# timetracker-1-5.net
KiCad netlist of a schematic drawn in EAGLE
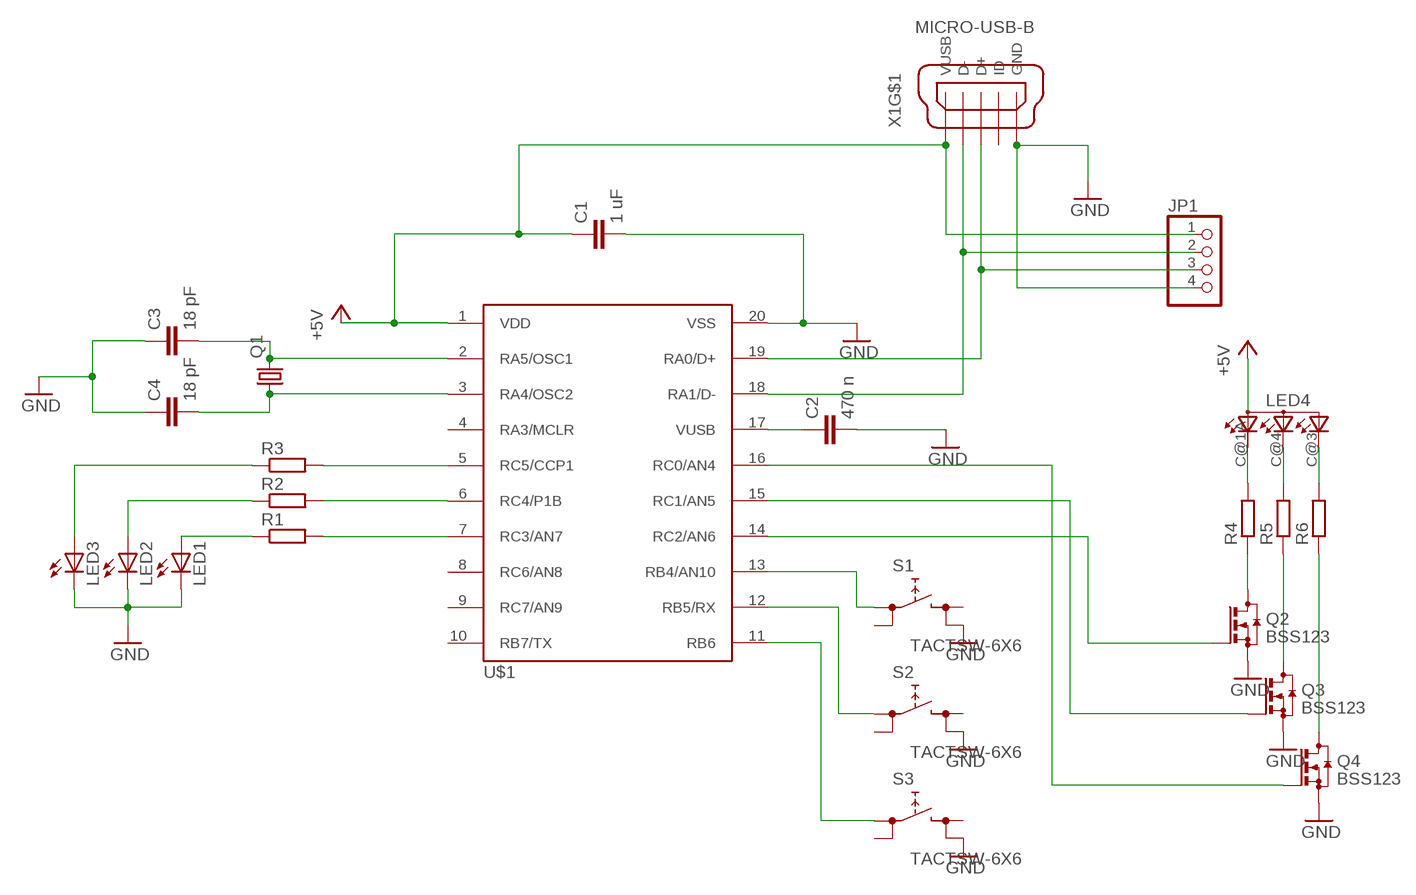
[diagram p0: schematic, sheet 1]

(export (version "E")
  (design (tool "Eeschema 10.0.6"))
  (components
    (comp (ref "C1")
      (value "1 uF")
      (footprint "eagle-import:C0805")
      (libsource (lib "eagle-import") (part "C-EUC0805"))
    )
    (comp (ref "C2")
      (value "470 n")
      (footprint "eagle-import:C0805")
      (libsource (lib "eagle-import") (part "C-EUC0805"))
    )
    (comp (ref "C3")
      (value "18 pF")
      (footprint "eagle-import:C0805")
      (libsource (lib "eagle-import") (part "C-EUC0805"))
    )
    (comp (ref "C4")
      (value "18 pF")
      (footprint "eagle-import:C0805")
      (libsource (lib "eagle-import") (part "C-EUC0805"))
    )
    (comp (ref "JP1")
      (value "PINHD-1X4")
      (footprint "eagle-import:1X04")
      (libsource (lib "eagle-import") (part "PINHD-1X4"))
    )
    (comp (ref "LED1")
      (value "LEDSML0805")
      (footprint "eagle-import:SML0805")
      (libsource (lib "eagle-import") (part "LEDSML0805"))
    )
    (comp (ref "LED2")
      (value "LEDSML0805")
      (footprint "eagle-import:SML0805")
      (libsource (lib "eagle-import") (part "LEDSML0805"))
    )
    (comp (ref "LED3")
      (value "LEDSML0805")
      (footprint "eagle-import:SML0805")
      (libsource (lib "eagle-import") (part "LEDSML0805"))
    )
    (comp (ref "LED4")
      (value "RGBLED-3P-LCC-4")
      (footprint "eagle-import:P-LCC-4")
      (libsource (lib "eagle-import") (part "RGBLED-3P-LCC-4"))
    )
    (comp (ref "Q1")
      (value "CRYSTALHC49UP")
      (footprint "eagle-import:HC49UP")
      (libsource (lib "eagle-import") (part "CRYSTALHC49UP"))
    )
    (comp (ref "Q2")
      (value "BSS123")
      (footprint "eagle-import:SOT23")
      (libsource (lib "eagle-import") (part "BSS123"))
    )
    (comp (ref "Q3")
      (value "BSS123")
      (footprint "eagle-import:SOT23")
      (libsource (lib "eagle-import") (part "BSS123"))
    )
    (comp (ref "Q4")
      (value "BSS123")
      (footprint "eagle-import:SOT23")
      (libsource (lib "eagle-import") (part "BSS123"))
    )
    (comp (ref "R1")
      (value "R-EU_R0805")
      (footprint "eagle-import:R0805")
      (libsource (lib "eagle-import") (part "R-EU_R0805"))
    )
    (comp (ref "R2")
      (value "R-EU_R0805")
      (footprint "eagle-import:R0805")
      (libsource (lib "eagle-import") (part "R-EU_R0805"))
    )
    (comp (ref "R3")
      (value "R-EU_R0805")
      (footprint "eagle-import:R0805")
      (libsource (lib "eagle-import") (part "R-EU_R0805"))
    )
    (comp (ref "R4")
      (value "R-EU_R0805")
      (footprint "eagle-import:R0805")
      (libsource (lib "eagle-import") (part "R-EU_R0805"))
    )
    (comp (ref "R5")
      (value "R-EU_R0805")
      (footprint "eagle-import:R0805")
      (libsource (lib "eagle-import") (part "R-EU_R0805"))
    )
    (comp (ref "R6")
      (value "R-EU_R0805")
      (footprint "eagle-import:R0805")
      (libsource (lib "eagle-import") (part "R-EU_R0805"))
    )
    (comp (ref "S1")
      (value "TACTSW-6X6")
      (footprint "eagle-import:TACTSW-6X6")
      (libsource (lib "eagle-import") (part "TACTSW-6X6"))
    )
    (comp (ref "S2")
      (value "TACTSW-6X6")
      (footprint "eagle-import:TACTSW-6X6")
      (libsource (lib "eagle-import") (part "TACTSW-6X6"))
    )
    (comp (ref "S3")
      (value "TACTSW-6X6")
      (footprint "eagle-import:TACTSW-6X6")
      (libsource (lib "eagle-import") (part "TACTSW-6X6"))
    )
    (comp (ref "U$1")
      (value "PIC18F14K50SMD")
      (footprint "eagle-import:DIL20-SMD")
      (libsource (lib "eagle-import") (part "PIC18F14K50SMD"))
    )
    (comp (ref "X1")
      (value "MICRO-USB-B")
      (footprint "eagle-import:MICRO-B-PAC")
      (libsource (lib "eagle-import") (part "MICRO-USB-B"))
    )
  )
  (nets
    (net (code "1") (name "+5V") (class "Default")
      (node (ref "C1") (pin "1") (pinfunction "1_1") (pintype "passive"))
      (node (ref "JP1") (pin "1") (pinfunction "1_1") (pintype "passive"))
      (node (ref "LED4") (pin "A") (pinfunction "A2_A") (pintype "passive"))
      (node (ref "U$1") (pin "1") (pinfunction "VDD_1") (pintype "bidirectional"))
      (node (ref "X1") (pin "1") (pinfunction "VUSB_1") (pintype "passive"))
    )
    (net (code "2") (name "GND") (class "Default")
      (node (ref "C1") (pin "2") (pinfunction "2_2") (pintype "passive"))
      (node (ref "C2") (pin "2") (pinfunction "2_2") (pintype "passive"))
      (node (ref "C3") (pin "1") (pinfunction "1_1") (pintype "passive"))
      (node (ref "C4") (pin "1") (pinfunction "1_1") (pintype "passive"))
      (node (ref "JP1") (pin "4") (pinfunction "4_4") (pintype "passive"))
      (node (ref "LED1") (pin "C") (pinfunction "C_C") (pintype "passive"))
      (node (ref "LED2") (pin "C") (pinfunction "C_C") (pintype "passive"))
      (node (ref "LED3") (pin "C") (pinfunction "C_C") (pintype "passive"))
      (node (ref "Q2") (pin "2") (pinfunction "S_2") (pintype "passive"))
      (node (ref "Q3") (pin "2") (pinfunction "S_2") (pintype "passive"))
      (node (ref "Q4") (pin "2") (pinfunction "S_2") (pintype "passive"))
      (node (ref "S1") (pin "4") (pinfunction "2.2_4") (pintype "passive"))
      (node (ref "S2") (pin "4") (pinfunction "2.2_4") (pintype "passive"))
      (node (ref "S3") (pin "4") (pinfunction "2.2_4") (pintype "passive"))
      (node (ref "U$1") (pin "20") (pinfunction "VSS_20") (pintype "bidirectional"))
      (node (ref "X1") (pin "5") (pinfunction "GND_5") (pintype "passive"))
    )
    (net (code "3") (name "Net-(LED1-PadA)") (class "Default")
      (node (ref "LED1") (pin "A") (pinfunction "A_A") (pintype "passive"))
      (node (ref "R1") (pin "1") (pinfunction "1_1") (pintype "passive"))
    )
    (net (code "4") (name "Net-(LED2-PadA)") (class "Default")
      (node (ref "LED2") (pin "A") (pinfunction "A_A") (pintype "passive"))
      (node (ref "R2") (pin "1") (pinfunction "1_1") (pintype "passive"))
    )
    (net (code "5") (name "Net-(LED3-PadA)") (class "Default")
      (node (ref "LED3") (pin "A") (pinfunction "A_A") (pintype "passive"))
      (node (ref "R3") (pin "1") (pinfunction "1_1") (pintype "passive"))
    )
    (net (code "6") (name "Net-(LED4-CBLUE)") (class "Default")
      (node (ref "LED4") (pin "C@3") (pinfunction "CBLUE_C@3") (pintype "passive"))
      (node (ref "R6") (pin "2") (pinfunction "2_2") (pintype "passive"))
    )
    (net (code "7") (name "Net-(LED4-CGREEN)") (class "Default")
      (node (ref "LED4") (pin "C@4") (pinfunction "CGREEN_C@4") (pintype "passive"))
      (node (ref "R5") (pin "2") (pinfunction "2_2") (pintype "passive"))
    )
    (net (code "8") (name "Net-(LED4-CRED)") (class "Default")
      (node (ref "LED4") (pin "C@1") (pinfunction "CRED_C@1") (pintype "passive"))
      (node (ref "R4") (pin "2") (pinfunction "2_2") (pintype "passive"))
    )
    (net (code "9") (name "Net-(Q2-D)") (class "Default")
      (node (ref "Q2") (pin "3") (pinfunction "D_3") (pintype "passive"))
      (node (ref "R4") (pin "1") (pinfunction "1_1") (pintype "passive"))
    )
    (net (code "10") (name "Net-(Q2-G)") (class "Default")
      (node (ref "Q2") (pin "1") (pinfunction "G_1") (pintype "passive"))
      (node (ref "U$1") (pin "14") (pinfunction "RC2/AN6_14") (pintype "bidirectional"))
    )
    (net (code "11") (name "Net-(Q3-D)") (class "Default")
      (node (ref "Q3") (pin "3") (pinfunction "D_3") (pintype "passive"))
      (node (ref "R5") (pin "1") (pinfunction "1_1") (pintype "passive"))
    )
    (net (code "12") (name "Net-(Q3-G)") (class "Default")
      (node (ref "Q3") (pin "1") (pinfunction "G_1") (pintype "passive"))
      (node (ref "U$1") (pin "15") (pinfunction "RC1/AN5_15") (pintype "bidirectional"))
    )
    (net (code "13") (name "Net-(Q4-D)") (class "Default")
      (node (ref "Q4") (pin "3") (pinfunction "D_3") (pintype "passive"))
      (node (ref "R6") (pin "1") (pinfunction "1_1") (pintype "passive"))
    )
    (net (code "14") (name "Net-(Q4-G)") (class "Default")
      (node (ref "Q4") (pin "1") (pinfunction "G_1") (pintype "passive"))
      (node (ref "U$1") (pin "16") (pinfunction "RC0/AN4_16") (pintype "bidirectional"))
    )
    (net (code "15") (name "Net-(S1-1.1)") (class "Default")
      (node (ref "S1") (pin "1") (pinfunction "1.1_1") (pintype "passive"))
      (node (ref "U$1") (pin "13") (pinfunction "RB4/AN10_13") (pintype "bidirectional"))
    )
    (net (code "16") (name "Net-(S2-1.1)") (class "Default")
      (node (ref "S2") (pin "1") (pinfunction "1.1_1") (pintype "passive"))
      (node (ref "U$1") (pin "12") (pinfunction "RB5/RX_12") (pintype "bidirectional"))
    )
    (net (code "17") (name "Net-(S3-1.1)") (class "Default")
      (node (ref "S3") (pin "1") (pinfunction "1.1_1") (pintype "passive"))
      (node (ref "U$1") (pin "11") (pinfunction "RB6_11") (pintype "bidirectional"))
    )
    (net (code "18") (name "Net-(U$1-RA0{slash}D+)") (class "Default")
      (node (ref "JP1") (pin "3") (pinfunction "3_3") (pintype "passive"))
      (node (ref "U$1") (pin "19") (pinfunction "RA0/D+_19") (pintype "bidirectional"))
      (node (ref "X1") (pin "3") (pinfunction "D+_3") (pintype "passive"))
    )
    (net (code "19") (name "Net-(U$1-RA1{slash}D-)") (class "Default")
      (node (ref "JP1") (pin "2") (pinfunction "2_2") (pintype "passive"))
      (node (ref "U$1") (pin "18") (pinfunction "RA1/D-_18") (pintype "bidirectional"))
      (node (ref "X1") (pin "2") (pinfunction "D-_2") (pintype "passive"))
    )
    (net (code "20") (name "Net-(U$1-RA4{slash}OSC2)") (class "Default")
      (node (ref "C4") (pin "2") (pinfunction "2_2") (pintype "passive"))
      (node (ref "Q1") (pin "1") (pinfunction "1_1") (pintype "passive"))
      (node (ref "U$1") (pin "3") (pinfunction "RA4/OSC2_3") (pintype "bidirectional"))
    )
    (net (code "21") (name "Net-(U$1-RA5{slash}OSC1)") (class "Default")
      (node (ref "C3") (pin "2") (pinfunction "2_2") (pintype "passive"))
      (node (ref "Q1") (pin "2") (pinfunction "2_2") (pintype "passive"))
      (node (ref "U$1") (pin "2") (pinfunction "RA5/OSC1_2") (pintype "bidirectional"))
    )
    (net (code "22") (name "Net-(U$1-RC3{slash}AN7)") (class "Default")
      (node (ref "R1") (pin "2") (pinfunction "2_2") (pintype "passive"))
      (node (ref "U$1") (pin "7") (pinfunction "RC3/AN7_7") (pintype "bidirectional"))
    )
    (net (code "23") (name "Net-(U$1-RC4{slash}P1B)") (class "Default")
      (node (ref "R2") (pin "2") (pinfunction "2_2") (pintype "passive"))
      (node (ref "U$1") (pin "6") (pinfunction "RC4/P1B_6") (pintype "bidirectional"))
    )
    (net (code "24") (name "Net-(U$1-RC5{slash}CCP1)") (class "Default")
      (node (ref "R3") (pin "2") (pinfunction "2_2") (pintype "passive"))
      (node (ref "U$1") (pin "5") (pinfunction "RC5/CCP1_5") (pintype "bidirectional"))
    )
    (net (code "25") (name "Net-(U$1-VUSB)") (class "Default")
      (node (ref "C2") (pin "1") (pinfunction "1_1") (pintype "passive"))
      (node (ref "U$1") (pin "17") (pinfunction "VUSB_17") (pintype "bidirectional"))
    )
    (net (code "26") (name "unconnected-(S1-1.2-Pad2)") (class "Default")
      (node (ref "S1") (pin "2") (pinfunction "1.2_2") (pintype "passive"))
    )
    (net (code "27") (name "unconnected-(S1-2.1-Pad3)") (class "Default")
      (node (ref "S1") (pin "3") (pinfunction "2.1_3") (pintype "passive"))
    )
    (net (code "28") (name "unconnected-(S2-1.2-Pad2)") (class "Default")
      (node (ref "S2") (pin "2") (pinfunction "1.2_2") (pintype "passive"))
    )
    (net (code "29") (name "unconnected-(S2-2.1-Pad3)") (class "Default")
      (node (ref "S2") (pin "3") (pinfunction "2.1_3") (pintype "passive"))
    )
    (net (code "30") (name "unconnected-(S3-1.2-Pad2)") (class "Default")
      (node (ref "S3") (pin "2") (pinfunction "1.2_2") (pintype "passive"))
    )
    (net (code "31") (name "unconnected-(S3-2.1-Pad3)") (class "Default")
      (node (ref "S3") (pin "3") (pinfunction "2.1_3") (pintype "passive"))
    )
    (net (code "32") (name "unconnected-(U$1-RA3{slash}MCLR-Pad4)") (class "Default")
      (node (ref "U$1") (pin "4") (pinfunction "RA3/MCLR_4") (pintype "bidirectional"))
    )
    (net (code "33") (name "unconnected-(U$1-RB7{slash}TX-Pad10)") (class "Default")
      (node (ref "U$1") (pin "10") (pinfunction "RB7/TX_10") (pintype "bidirectional"))
    )
    (net (code "34") (name "unconnected-(U$1-RC6{slash}AN8-Pad8)") (class "Default")
      (node (ref "U$1") (pin "8") (pinfunction "RC6/AN8_8") (pintype "bidirectional"))
    )
    (net (code "35") (name "unconnected-(U$1-RC7{slash}AN9-Pad9)") (class "Default")
      (node (ref "U$1") (pin "9") (pinfunction "RC7/AN9_9") (pintype "bidirectional"))
    )
    (net (code "36") (name "unconnected-(X1A-ID-Pad4)") (class "Default")
      (node (ref "X1") (pin "4") (pinfunction "ID_4") (pintype "passive"))
    )
  )
)
